# Shield_pololu.net
KiCad netlist of a schematic drawn in EAGLE
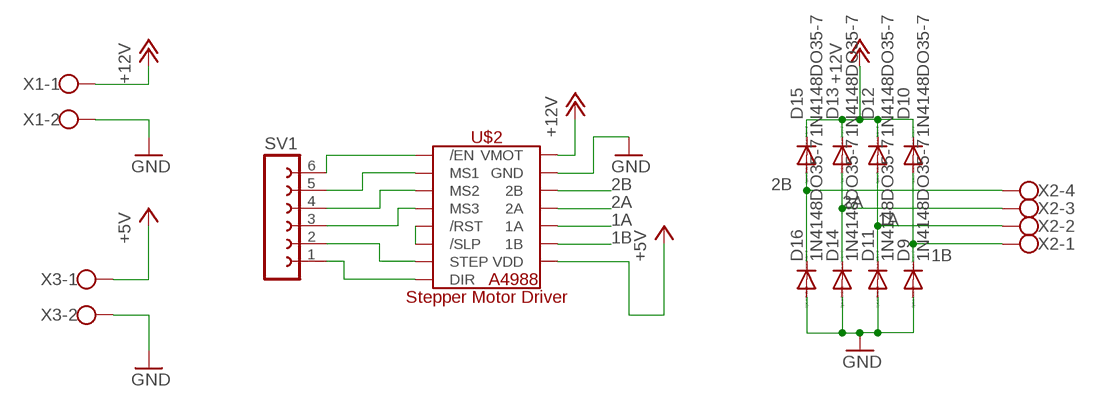
[diagram p0: schematic, sheet 1]

(export (version "E")
  (design (tool "Eeschema 10.0.6"))
  (components
    (comp (ref "D9")
      (value "1N4148DO35-7")
      (footprint "eagle-import:DO35-7")
      (libsource (lib "eagle-import") (part "1N4148DO35-7"))
    )
    (comp (ref "D10")
      (value "1N4148DO35-7")
      (footprint "eagle-import:DO35-7")
      (libsource (lib "eagle-import") (part "1N4148DO35-7"))
    )
    (comp (ref "D11")
      (value "1N4148DO35-7")
      (footprint "eagle-import:DO35-7")
      (libsource (lib "eagle-import") (part "1N4148DO35-7"))
    )
    (comp (ref "D12")
      (value "1N4148DO35-7")
      (footprint "eagle-import:DO35-7")
      (libsource (lib "eagle-import") (part "1N4148DO35-7"))
    )
    (comp (ref "D13")
      (value "1N4148DO35-7")
      (footprint "eagle-import:DO35-7")
      (libsource (lib "eagle-import") (part "1N4148DO35-7"))
    )
    (comp (ref "D14")
      (value "1N4148DO35-7")
      (footprint "eagle-import:DO35-7")
      (libsource (lib "eagle-import") (part "1N4148DO35-7"))
    )
    (comp (ref "D15")
      (value "1N4148DO35-7")
      (footprint "eagle-import:DO35-7")
      (libsource (lib "eagle-import") (part "1N4148DO35-7"))
    )
    (comp (ref "D16")
      (value "1N4148DO35-7")
      (footprint "eagle-import:DO35-7")
      (libsource (lib "eagle-import") (part "1N4148DO35-7"))
    )
    (comp (ref "SV1")
      (value "FE06-1")
      (footprint "eagle-import:FE06")
      (libsource (lib "eagle-import") (part "FE06-1"))
    )
    (comp (ref "U$2")
      (value "A4988_STEP")
      (footprint "eagle-import:A4988_STEP")
      (libsource (lib "eagle-import") (part "A4988_STEP"))
    )
    (comp (ref "X1")
      (value "W237-102")
      (footprint "eagle-import:W237-102")
      (fields (field (name "MPN") "237-102"))
      (libsource (lib "eagle-import") (part "W237-102"))
    )
    (comp (ref "X2")
      (value "W237-4")
      (footprint "eagle-import:W237-4")
      (libsource (lib "eagle-import") (part "W237-4"))
    )
    (comp (ref "X3")
      (value "W237-102")
      (footprint "eagle-import:W237-102")
      (fields (field (name "MPN") "237-102"))
      (libsource (lib "eagle-import") (part "W237-102"))
    )
  )
  (nets
    (net (code "1") (name "+5V") (class "Default")
      (node (ref "U$2") (pin "VDD") (pinfunction "VDD_VDD") (pintype "bidirectional"))
      (node (ref "X3") (pin "1") (pinfunction "KL_1") (pintype "passive"))
    )
    (net (code "2") (name "+12V") (class "Default")
      (node (ref "D10") (pin "C") (pinfunction "C_C") (pintype "passive"))
      (node (ref "D12") (pin "C") (pinfunction "C_C") (pintype "passive"))
      (node (ref "D13") (pin "C") (pinfunction "C_C") (pintype "passive"))
      (node (ref "D15") (pin "C") (pinfunction "C_C") (pintype "passive"))
      (node (ref "U$2") (pin "VMOT") (pinfunction "VMOT_VMOT") (pintype "bidirectional"))
      (node (ref "X1") (pin "1") (pinfunction "KL_1") (pintype "passive"))
    )
    (net (code "3") (name "/1A") (class "Default")
      (node (ref "D11") (pin "C") (pinfunction "C_C") (pintype "passive"))
      (node (ref "D12") (pin "A") (pinfunction "A_A") (pintype "passive"))
      (node (ref "U$2") (pin "1A") (pinfunction "1A_1A") (pintype "bidirectional"))
      (node (ref "X2") (pin "2") (pinfunction "KL_2") (pintype "passive"))
    )
    (net (code "4") (name "/1B") (class "Default")
      (node (ref "D10") (pin "A") (pinfunction "A_A") (pintype "passive"))
      (node (ref "D9") (pin "C") (pinfunction "C_C") (pintype "passive"))
      (node (ref "U$2") (pin "1B") (pinfunction "1B_1B") (pintype "bidirectional"))
      (node (ref "X2") (pin "1") (pinfunction "KL_1") (pintype "passive"))
    )
    (net (code "5") (name "/2A") (class "Default")
      (node (ref "D13") (pin "A") (pinfunction "A_A") (pintype "passive"))
      (node (ref "D14") (pin "C") (pinfunction "C_C") (pintype "passive"))
      (node (ref "U$2") (pin "2A") (pinfunction "2A_2A") (pintype "bidirectional"))
      (node (ref "X2") (pin "3") (pinfunction "KL_3") (pintype "passive"))
    )
    (net (code "6") (name "/2B") (class "Default")
      (node (ref "D15") (pin "A") (pinfunction "A_A") (pintype "passive"))
      (node (ref "D16") (pin "C") (pinfunction "C_C") (pintype "passive"))
      (node (ref "U$2") (pin "2B") (pinfunction "2B_2B") (pintype "bidirectional"))
      (node (ref "X2") (pin "4") (pinfunction "KL_4") (pintype "passive"))
    )
    (net (code "7") (name "GND") (class "Default")
      (node (ref "D11") (pin "A") (pinfunction "A_A") (pintype "passive"))
      (node (ref "D14") (pin "A") (pinfunction "A_A") (pintype "passive"))
      (node (ref "D16") (pin "A") (pinfunction "A_A") (pintype "passive"))
      (node (ref "D9") (pin "A") (pinfunction "A_A") (pintype "passive"))
      (node (ref "U$2") (pin "GND") (pinfunction "GND_GND") (pintype "bidirectional"))
      (node (ref "U$2") (pin "GND2") (pinfunction "GND_GND2") (pintype "bidirectional"))
      (node (ref "X1") (pin "2") (pinfunction "KL_2") (pintype "passive"))
      (node (ref "X3") (pin "2") (pinfunction "KL_2") (pintype "passive"))
    )
    (net (code "8") (name "Net-(SV1-Pad1)") (class "Default")
      (node (ref "SV1") (pin "1") (pinfunction "1_1") (pintype "passive"))
      (node (ref "U$2") (pin "DIR") (pinfunction "DIR_DIR") (pintype "bidirectional"))
    )
    (net (code "9") (name "Net-(SV1-Pad2)") (class "Default")
      (node (ref "SV1") (pin "2") (pinfunction "2_2") (pintype "passive"))
      (node (ref "U$2") (pin "STEP") (pinfunction "STEP_STEP") (pintype "bidirectional"))
    )
    (net (code "10") (name "Net-(SV1-Pad3)") (class "Default")
      (node (ref "SV1") (pin "3") (pinfunction "3_3") (pintype "passive"))
      (node (ref "U$2") (pin "MS3") (pinfunction "MS3_MS3") (pintype "bidirectional"))
    )
    (net (code "11") (name "Net-(SV1-Pad4)") (class "Default")
      (node (ref "SV1") (pin "4") (pinfunction "4_4") (pintype "passive"))
      (node (ref "U$2") (pin "MS2") (pinfunction "MS2_MS2") (pintype "bidirectional"))
    )
    (net (code "12") (name "Net-(SV1-Pad5)") (class "Default")
      (node (ref "SV1") (pin "5") (pinfunction "5_5") (pintype "passive"))
      (node (ref "U$2") (pin "MS1") (pinfunction "MS1_MS1") (pintype "bidirectional"))
    )
    (net (code "13") (name "Net-(SV1-Pad6)") (class "Default")
      (node (ref "SV1") (pin "6") (pinfunction "6_6") (pintype "passive"))
      (node (ref "U$2") (pin "/EN") (pinfunction "/EN_/EN") (pintype "bidirectional"))
    )
    (net (code "14") (name "Net-(U$2-Pad{slash}RST)") (class "Default")
      (node (ref "U$2") (pin "/RST") (pinfunction "/RST_/RST") (pintype "bidirectional"))
      (node (ref "U$2") (pin "/SLP") (pinfunction "/SLP_/SLP") (pintype "bidirectional"))
    )
  )
)
